# NRF24L01P.net
KiCad netlist of a schematic drawn in Altium Designer
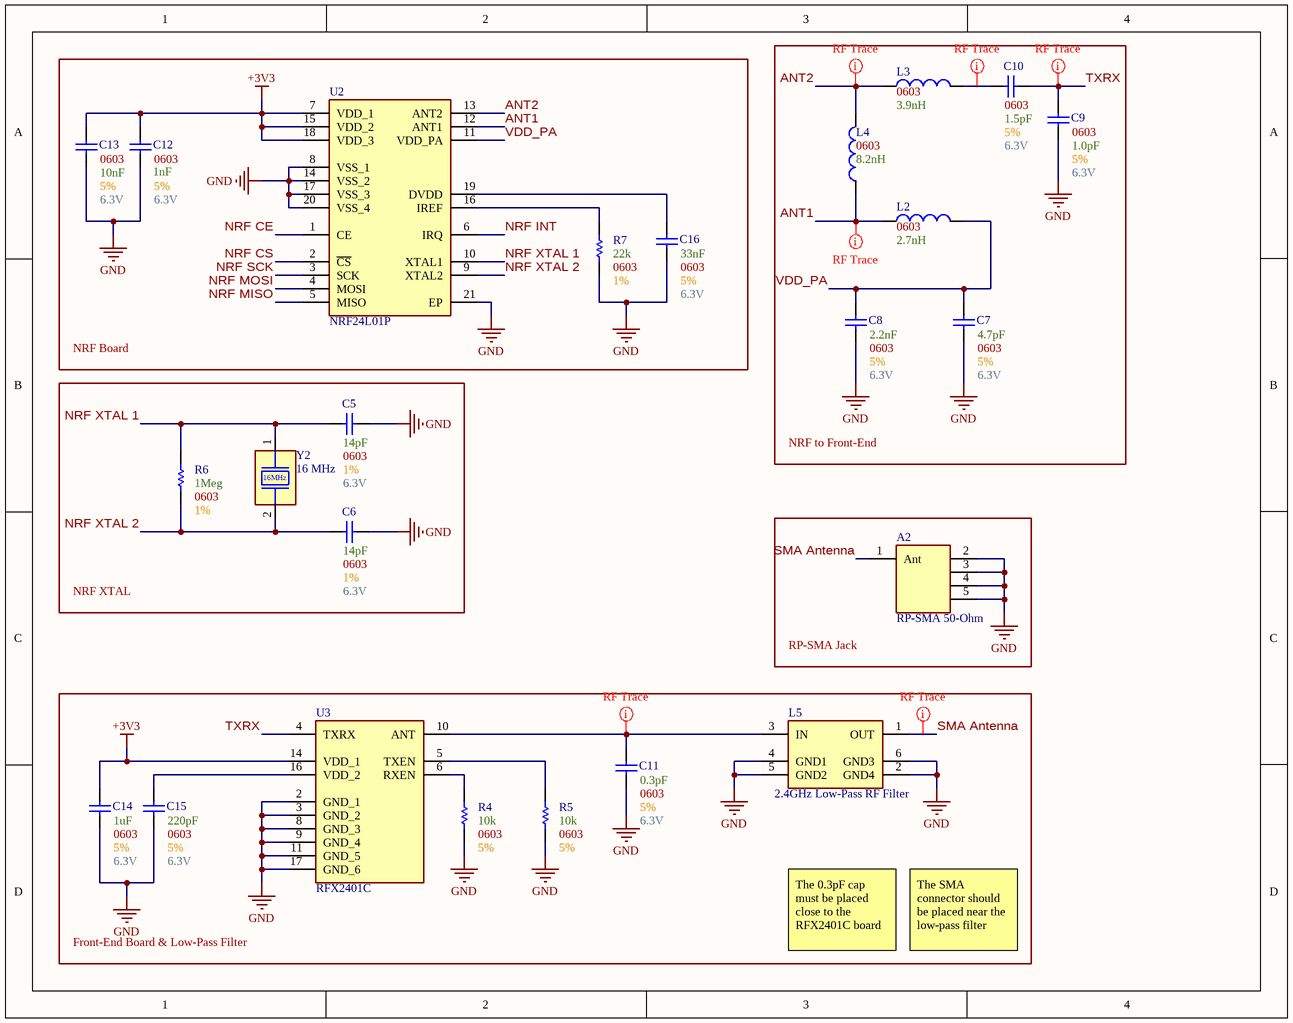
[diagram p0: NRF24L01P.SchDoc]

(export (version "E")
  (design (tool "Eeschema 10.0.6"))
  (components
    (comp (ref "A2")
      (value "RP-SMA 50-Ohm")
      (footprint "[SMA] RP-SMA 90deg Jack")
      (description "PCB.RPSMAFRA.HT")
      (libsource (lib "RADM Connectors") (part "[SMA] RP-SMA 90deg Jack"))
    )
    (comp (ref "C5")
      (value "SMD Nonpolarized")
      (footprint "[Cap] SMD 0603")
      (fields
        (field (name "TOLERANCE") "1%")
        (field (name "SIZE PACKAGE") "0603")
        (field (name "CAPACITANCE") "14pF")
        (field (name "VOLTAGE") "6.3V")
      )
      (libsource (lib "RADM Components") (part "[Cap] SMD Nonpolarized"))
    )
    (comp (ref "C6")
      (value "SMD Nonpolarized")
      (footprint "[Cap] SMD 0603")
      (fields
        (field (name "TOLERANCE") "1%")
        (field (name "SIZE PACKAGE") "0603")
        (field (name "CAPACITANCE") "14pF")
        (field (name "VOLTAGE") "6.3V")
      )
      (libsource (lib "RADM Components") (part "[Cap] SMD Nonpolarized"))
    )
    (comp (ref "C7")
      (value "SMD Nonpolarized")
      (footprint "[Cap] SMD 0603")
      (fields
        (field (name "TOLERANCE") "5%")
        (field (name "SIZE PACKAGE") "0603")
        (field (name "CAPACITANCE") "4.7pF")
        (field (name "VOLTAGE") "6.3V")
      )
      (libsource (lib "RADM Components") (part "[Cap] SMD Nonpolarized"))
    )
    (comp (ref "C8")
      (value "SMD Nonpolarized")
      (footprint "[Cap] SMD 0603")
      (fields
        (field (name "TOLERANCE") "5%")
        (field (name "SIZE PACKAGE") "0603")
        (field (name "CAPACITANCE") "2.2nF")
        (field (name "VOLTAGE") "6.3V")
      )
      (libsource (lib "RADM Components") (part "[Cap] SMD Nonpolarized"))
    )
    (comp (ref "C9")
      (value "SMD Nonpolarized")
      (footprint "[Cap] SMD 0603")
      (fields
        (field (name "TOLERANCE") "5%")
        (field (name "SIZE PACKAGE") "0603")
        (field (name "CAPACITANCE") "1.0pF")
        (field (name "VOLTAGE") "6.3V")
      )
      (libsource (lib "RADM Components") (part "[Cap] SMD Nonpolarized"))
    )
    (comp (ref "C10")
      (value "SMD Nonpolarized")
      (footprint "[Cap] SMD 0603")
      (fields
        (field (name "TOLERANCE") "5%")
        (field (name "SIZE PACKAGE") "0603")
        (field (name "CAPACITANCE") "1.5pF")
        (field (name "VOLTAGE") "6.3V")
      )
      (libsource (lib "RADM Components") (part "[Cap] SMD Nonpolarized"))
    )
    (comp (ref "C11")
      (value "SMD Nonpolarized")
      (footprint "[Cap] SMD 0603")
      (fields
        (field (name "TOLERANCE") "5%")
        (field (name "SIZE PACKAGE") "0603")
        (field (name "CAPACITANCE") "0.3pF")
        (field (name "VOLTAGE") "6.3V")
      )
      (libsource (lib "RADM Components") (part "[Cap] SMD Nonpolarized"))
    )
    (comp (ref "C12")
      (value "SMD Nonpolarized")
      (footprint "[Cap] SMD 0603")
      (fields
        (field (name "TOLERANCE") "5%")
        (field (name "SIZE PACKAGE") "0603")
        (field (name "CAPACITANCE") "1nF")
        (field (name "VOLTAGE") "6.3V")
      )
      (libsource (lib "RADM Components") (part "[Cap] SMD Nonpolarized"))
    )
    (comp (ref "C13")
      (value "SMD Nonpolarized")
      (footprint "[Cap] SMD 0603")
      (fields
        (field (name "TOLERANCE") "5%")
        (field (name "SIZE PACKAGE") "0603")
        (field (name "CAPACITANCE") "10nF")
        (field (name "VOLTAGE") "6.3V")
      )
      (libsource (lib "RADM Components") (part "[Cap] SMD Nonpolarized"))
    )
    (comp (ref "C14")
      (value "SMD Nonpolarized")
      (footprint "[Cap] SMD 0603")
      (fields
        (field (name "TOLERANCE") "5%")
        (field (name "SIZE PACKAGE") "0603")
        (field (name "CAPACITANCE") "1uF")
        (field (name "VOLTAGE") "6.3V")
      )
      (libsource (lib "RADM Components") (part "[Cap] SMD Nonpolarized"))
    )
    (comp (ref "C15")
      (value "SMD Nonpolarized")
      (footprint "[Cap] SMD 0603")
      (fields
        (field (name "TOLERANCE") "5%")
        (field (name "SIZE PACKAGE") "0603")
        (field (name "CAPACITANCE") "220pF")
        (field (name "VOLTAGE") "6.3V")
      )
      (libsource (lib "RADM Components") (part "[Cap] SMD Nonpolarized"))
    )
    (comp (ref "C16")
      (value "SMD Nonpolarized")
      (footprint "[Cap] SMD 0603")
      (fields
        (field (name "TOLERANCE") "5%")
        (field (name "SIZE PACKAGE") "0603")
        (field (name "CAPACITANCE") "33nF")
        (field (name "VOLTAGE") "6.3V")
      )
      (libsource (lib "RADM Components") (part "[Cap] SMD Nonpolarized"))
    )
    (comp (ref "L2")
      (value "SMD Inductor")
      (footprint "[Inductor] SMD 0603")
      (fields (field (name "SIZE PACKAGE") "0603") (field (name "INDUCTANCE") "2.7nH"))
      (libsource (lib "RADM Components") (part "[Inductor] SMD Inductor"))
    )
    (comp (ref "L3")
      (value "SMD Inductor")
      (footprint "[Inductor] SMD 0603")
      (fields (field (name "SIZE PACKAGE") "0603") (field (name "INDUCTANCE") "3.9nH"))
      (libsource (lib "RADM Components") (part "[Inductor] SMD Inductor"))
    )
    (comp (ref "L4")
      (value "SMD Inductor")
      (footprint "[Inductor] SMD 0603")
      (fields (field (name "SIZE PACKAGE") "0603") (field (name "INDUCTANCE") "8.2nH"))
      (libsource (lib "RADM Components") (part "[Inductor] SMD Inductor"))
    )
    (comp (ref "L5")
      (value "2.4GHz Low-Pass RF Filter")
      (footprint "[Inductor] 2.4GHz Low-Pass RF Filter")
      (description "MLPF-NRG-01D3")
      (libsource (lib "RADM Components") (part "[Inductor] 2.4GHz Low-Pass RF Filter"))
    )
    (comp (ref "R4")
      (value "[Res] SMD Resistor")
      (footprint "[Res] SMD 0603")
      (description "Generic")
      (fields
        (field (name "TOLERANCE") "5%")
        (field (name "RESISTANCE") "10k")
        (field (name "SIZE PACKAGE") "0603")
      )
      (libsource (lib "RADM Components") (part "[Res] SMD Resistor"))
    )
    (comp (ref "R5")
      (value "[Res] SMD Resistor")
      (footprint "[Res] SMD 0603")
      (description "Generic")
      (fields
        (field (name "TOLERANCE") "5%")
        (field (name "RESISTANCE") "10k")
        (field (name "SIZE PACKAGE") "0603")
      )
      (libsource (lib "RADM Components") (part "[Res] SMD Resistor"))
    )
    (comp (ref "R6")
      (value "[Res] SMD Resistor")
      (footprint "[Res] SMD 0603")
      (description "Generic")
      (fields
        (field (name "TOLERANCE") "1%")
        (field (name "RESISTANCE") "1Meg")
        (field (name "SIZE PACKAGE") "0603")
      )
      (libsource (lib "RADM Components") (part "[Res] SMD Resistor"))
    )
    (comp (ref "R7")
      (value "[Res] SMD Resistor")
      (footprint "[Res] SMD 0603")
      (description "Generic")
      (fields
        (field (name "TOLERANCE") "1%")
        (field (name "RESISTANCE") "22k")
        (field (name "SIZE PACKAGE") "0603")
      )
      (libsource (lib "RADM Components") (part "[Res] SMD Resistor"))
    )
    (comp (ref "U2")
      (value "NRF24L01P")
      (footprint "[IC] NRF Transceiver")
      (description "NRF24L01P-R")
      (libsource (lib "RADM Components") (part "[IC] NRF Transceiver"))
    )
    (comp (ref "U3")
      (value "RFX2401C")
      (footprint "[IC] RF Front-End")
      (libsource (lib "RADM Components") (part "[IC] RF Front-End"))
    )
    (comp (ref "Y2")
      (value "16 MHz")
      (footprint "[XTAL] SMD 16MHz (2)")
      (description "ABM11-16.000MHZ-12-N1G-T")
      (libsource (lib "RADM Components") (part "[XTAL] SMD 16MHz (2)"))
    )
  )
  (nets
    (net (code "1") (name "+3V3") (class "Default")
      (node (ref "C12") (pin "2") (pinfunction "2_2") (pintype "passive"))
      (node (ref "C13") (pin "2") (pinfunction "2_2") (pintype "passive"))
      (node (ref "C14") (pin "2") (pinfunction "2_2") (pintype "passive"))
      (node (ref "U2") (pin "15") (pinfunction "VDD_2_15") (pintype "passive"))
      (node (ref "U2") (pin "18") (pinfunction "VDD_3_18") (pintype "passive"))
      (node (ref "U2") (pin "7") (pinfunction "VDD_1_7") (pintype "passive"))
      (node (ref "U3") (pin "14") (pinfunction "VDD_1_14") (pintype "passive"))
    )
    (net (code "2") (name "/ANT1") (class "Default")
      (node (ref "L2") (pin "1") (pinfunction "1_1") (pintype "passive"))
      (node (ref "L4") (pin "1") (pinfunction "1_1") (pintype "passive"))
      (node (ref "U2") (pin "12") (pinfunction "ANT1_12") (pintype "passive"))
    )
    (net (code "3") (name "/ANT2") (class "Default")
      (node (ref "L3") (pin "1") (pinfunction "1_1") (pintype "passive"))
      (node (ref "L4") (pin "2") (pinfunction "2_2") (pintype "passive"))
      (node (ref "U2") (pin "13") (pinfunction "ANT2_13") (pintype "passive"))
    )
    (net (code "4") (name "/NRF CE") (class "Default")
      (node (ref "U2") (pin "1") (pinfunction "CE_1") (pintype "passive"))
    )
    (net (code "5") (name "/NRF CS") (class "Default")
      (node (ref "U2") (pin "2") (pinfunction "CS_2") (pintype "passive"))
    )
    (net (code "6") (name "/NRF INT") (class "Default")
      (node (ref "U2") (pin "6") (pinfunction "IRQ_6") (pintype "passive"))
    )
    (net (code "7") (name "/NRF MISO") (class "Default")
      (node (ref "U2") (pin "5") (pinfunction "MISO_5") (pintype "passive"))
    )
    (net (code "8") (name "/NRF MOSI") (class "Default")
      (node (ref "U2") (pin "4") (pinfunction "MOSI_4") (pintype "passive"))
    )
    (net (code "9") (name "/NRF SCK") (class "Default")
      (node (ref "U2") (pin "3") (pinfunction "SCK_3") (pintype "passive"))
    )
    (net (code "10") (name "/NRF XTAL 1") (class "Default")
      (node (ref "C5") (pin "1") (pinfunction "1_1") (pintype "passive"))
      (node (ref "R6") (pin "1") (pinfunction "1_1") (pintype "passive"))
      (node (ref "U2") (pin "10") (pinfunction "XTAL1_10") (pintype "passive"))
      (node (ref "Y2") (pin "1") (pinfunction "XTAL1_1") (pintype "passive"))
    )
    (net (code "11") (name "/NRF XTAL 2") (class "Default")
      (node (ref "C6") (pin "1") (pinfunction "1_1") (pintype "passive"))
      (node (ref "R6") (pin "2") (pinfunction "2_2") (pintype "passive"))
      (node (ref "U2") (pin "9") (pinfunction "XTAL2_9") (pintype "passive"))
      (node (ref "Y2") (pin "2") (pinfunction "XTAL2_2") (pintype "passive"))
    )
    (net (code "12") (name "/SMA Antenna") (class "Default")
      (node (ref "A2") (pin "1") (pinfunction "Ant_1") (pintype "passive"))
      (node (ref "L5") (pin "1") (pinfunction "OUT_1") (pintype "passive"))
    )
    (net (code "13") (name "/TXRX") (class "Default")
      (node (ref "C10") (pin "1") (pinfunction "1_1") (pintype "passive"))
      (node (ref "C9") (pin "1") (pinfunction "1_1") (pintype "passive"))
      (node (ref "U3") (pin "4") (pinfunction "TXRX_4") (pintype "passive"))
    )
    (net (code "14") (name "/VDD_PA") (class "Default")
      (node (ref "C7") (pin "2") (pinfunction "2_2") (pintype "passive"))
      (node (ref "C8") (pin "2") (pinfunction "2_2") (pintype "passive"))
      (node (ref "L2") (pin "2") (pinfunction "2_2") (pintype "passive"))
      (node (ref "U2") (pin "11") (pinfunction "VDD_PA_11") (pintype "passive"))
    )
    (net (code "15") (name "GND") (class "Default")
      (node (ref "A2") (pin "2") (pinfunction "2_2") (pintype "passive"))
      (node (ref "A2") (pin "3") (pinfunction "3_3") (pintype "passive"))
      (node (ref "A2") (pin "4") (pinfunction "4_4") (pintype "passive"))
      (node (ref "A2") (pin "5") (pinfunction "5_5") (pintype "passive"))
      (node (ref "C11") (pin "1") (pinfunction "1_1") (pintype "passive"))
      (node (ref "C12") (pin "1") (pinfunction "1_1") (pintype "passive"))
      (node (ref "C13") (pin "1") (pinfunction "1_1") (pintype "passive"))
      (node (ref "C14") (pin "1") (pinfunction "1_1") (pintype "passive"))
      (node (ref "C15") (pin "1") (pinfunction "1_1") (pintype "passive"))
      (node (ref "C16") (pin "1") (pinfunction "1_1") (pintype "passive"))
      (node (ref "C5") (pin "2") (pinfunction "2_2") (pintype "passive"))
      (node (ref "C6") (pin "2") (pinfunction "2_2") (pintype "passive"))
      (node (ref "C7") (pin "1") (pinfunction "1_1") (pintype "passive"))
      (node (ref "C8") (pin "1") (pinfunction "1_1") (pintype "passive"))
      (node (ref "C9") (pin "2") (pinfunction "2_2") (pintype "passive"))
      (node (ref "L5") (pin "2") (pinfunction "GND4_2") (pintype "passive"))
      (node (ref "L5") (pin "4") (pinfunction "GND1_4") (pintype "passive"))
      (node (ref "L5") (pin "5") (pinfunction "GND2_5") (pintype "passive"))
      (node (ref "L5") (pin "6") (pinfunction "GND3_6") (pintype "passive"))
      (node (ref "R4") (pin "1") (pinfunction "1_1") (pintype "passive"))
      (node (ref "R5") (pin "1") (pinfunction "1_1") (pintype "passive"))
      (node (ref "R7") (pin "1") (pinfunction "1_1") (pintype "passive"))
      (node (ref "U2") (pin "14") (pinfunction "VSS_2_14") (pintype "passive"))
      (node (ref "U2") (pin "17") (pinfunction "VSS_3_17") (pintype "passive"))
      (node (ref "U2") (pin "20") (pinfunction "VSS_4_20") (pintype "passive"))
      (node (ref "U2") (pin "21") (pinfunction "EP_21") (pintype "passive"))
      (node (ref "U2") (pin "8") (pinfunction "VSS_1_8") (pintype "passive"))
      (node (ref "U3") (pin "11") (pinfunction "GND_5_11") (pintype "passive"))
      (node (ref "U3") (pin "17") (pinfunction "GND_6_17") (pintype "passive"))
      (node (ref "U3") (pin "2") (pinfunction "GND_1_2") (pintype "passive"))
      (node (ref "U3") (pin "3") (pinfunction "GND_2_3") (pintype "passive"))
      (node (ref "U3") (pin "8") (pinfunction "GND_3_8") (pintype "passive"))
      (node (ref "U3") (pin "9") (pinfunction "GND_4_9") (pintype "passive"))
    )
    (net (code "16") (name "Net-(C10-Pad2)") (class "Default")
      (node (ref "C10") (pin "2") (pinfunction "2_2") (pintype "passive"))
      (node (ref "L3") (pin "2") (pinfunction "2_2") (pintype "passive"))
    )
    (net (code "17") (name "Net-(L5-IN)") (class "Default")
      (node (ref "C11") (pin "2") (pinfunction "2_2") (pintype "passive"))
      (node (ref "L5") (pin "3") (pinfunction "IN_3") (pintype "passive"))
      (node (ref "U3") (pin "10") (pinfunction "ANT_10") (pintype "passive"))
    )
    (net (code "18") (name "Net-(U2-DVDD)") (class "Default")
      (node (ref "C16") (pin "2") (pinfunction "2_2") (pintype "passive"))
      (node (ref "U2") (pin "19") (pinfunction "DVDD_19") (pintype "passive"))
    )
    (net (code "19") (name "Net-(U2-IREF)") (class "Default")
      (node (ref "R7") (pin "2") (pinfunction "2_2") (pintype "passive"))
      (node (ref "U2") (pin "16") (pinfunction "IREF_16") (pintype "passive"))
    )
    (net (code "20") (name "Net-(U3-RXEN)") (class "Default")
      (node (ref "R4") (pin "2") (pinfunction "2_2") (pintype "passive"))
      (node (ref "U3") (pin "6") (pinfunction "RXEN_6") (pintype "passive"))
    )
    (net (code "21") (name "Net-(U3-TXEN)") (class "Default")
      (node (ref "R5") (pin "2") (pinfunction "2_2") (pintype "passive"))
      (node (ref "U3") (pin "5") (pinfunction "TXEN_5") (pintype "passive"))
    )
    (net (code "22") (name "Net-(U3-VDD_2)") (class "Default")
      (node (ref "C15") (pin "2") (pinfunction "2_2") (pintype "passive"))
      (node (ref "U3") (pin "16") (pinfunction "VDD_2_16") (pintype "passive"))
    )
  )
)
